# ProPrj_EMU_Multi_LED_Button_PCB_rev1_1.net
KiCad netlist of a schematic drawn in EasyEDA Pro
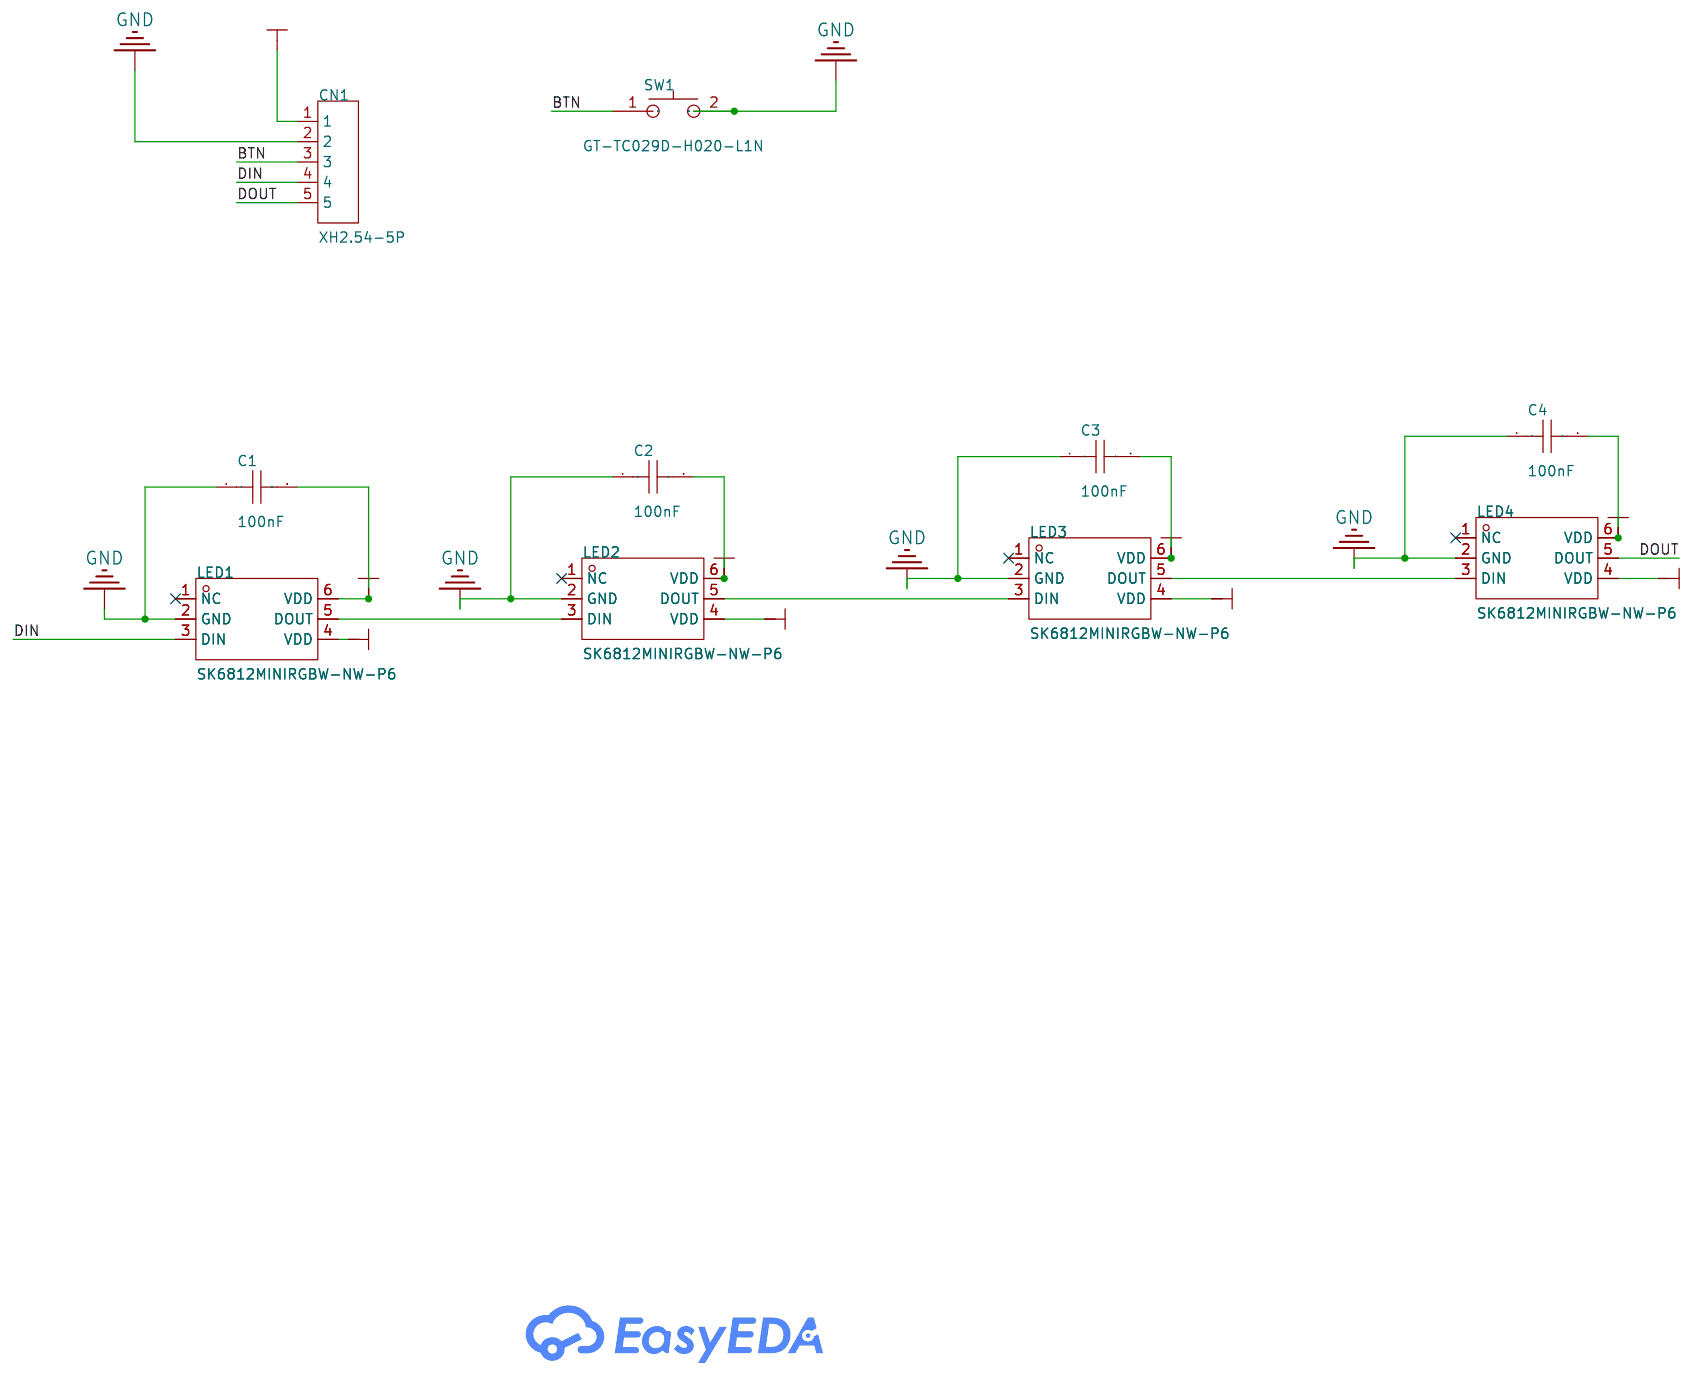
[diagram p0: schematic sheet]

(export (version "E")
  (design (tool "Eeschema 10.0.6"))
  (components
    (comp (ref "C1")
      (value "100nF")
      (footprint "easyedapro:C0603")
      (description "Capacitance:100nF Tolerance:±10% Tolerance:±10% Voltage Rating:50V Temperature Coefficient:X7R")
      (fields
        (field (name "Manufacturer Part") "CC0603KRX7R9BB104")
        (field (name "Manufacturer") "YAGEO(国巨)")
      )
      (libsource (lib "easyedapro") (part "CC0603KRX7R9BB104"))
    )
    (comp (ref "C2")
      (value "100nF")
      (footprint "easyedapro:C0603")
      (description "Capacitance:100nF Tolerance:±10% Tolerance:±10% Voltage Rating:50V Temperature Coefficient:X7R")
      (fields
        (field (name "Manufacturer Part") "CC0603KRX7R9BB104")
        (field (name "Manufacturer") "YAGEO(国巨)")
      )
      (libsource (lib "easyedapro") (part "CC0603KRX7R9BB104"))
    )
    (comp (ref "C3")
      (value "100nF")
      (footprint "easyedapro:C0603")
      (description "Capacitance:100nF Tolerance:±10% Tolerance:±10% Voltage Rating:50V Temperature Coefficient:X7R")
      (fields
        (field (name "Manufacturer Part") "CC0603KRX7R9BB104")
        (field (name "Manufacturer") "YAGEO(国巨)")
      )
      (libsource (lib "easyedapro") (part "CC0603KRX7R9BB104"))
    )
    (comp (ref "C4")
      (value "100nF")
      (footprint "easyedapro:C0603")
      (description "Capacitance:100nF Tolerance:±10% Tolerance:±10% Voltage Rating:50V Temperature Coefficient:X7R")
      (fields
        (field (name "Manufacturer Part") "CC0603KRX7R9BB104")
        (field (name "Manufacturer") "YAGEO(国巨)")
      )
      (libsource (lib "easyedapro") (part "CC0603KRX7R9BB104"))
    )
    (comp (ref "CN1")
      (value "XH2.54-5P")
      (footprint "easyedapro:CONN-TH_5P-P2.54_C9900008095")
      (libsource (lib "easyedapro") (part "XH2.54-5P_C9900017328"))
    )
    (comp (ref "LED1")
      (value "SK6812MINIRGBW-NW-P6")
      (footprint "easyedapro:LED-ARRAY-SMD_6P-L3.7-W3.5-TL-RD-1")
      (fields (field (name "Manufacturer") "欧思科光电"))
      (libsource (lib "easyedapro") (part "SK6812MINIRGBW-NW-P6"))
    )
    (comp (ref "LED2")
      (value "SK6812MINIRGBW-NW-P6")
      (footprint "easyedapro:LED-ARRAY-SMD_6P-L3.7-W3.5-TL-RD-1")
      (fields (field (name "Manufacturer") "欧思科光电"))
      (libsource (lib "easyedapro") (part "SK6812MINIRGBW-NW-P6"))
    )
    (comp (ref "LED3")
      (value "SK6812MINIRGBW-NW-P6")
      (footprint "easyedapro:LED-ARRAY-SMD_6P-L3.7-W3.5-TL-RD-1")
      (fields (field (name "Manufacturer") "欧思科光电"))
      (libsource (lib "easyedapro") (part "SK6812MINIRGBW-NW-P6"))
    )
    (comp (ref "LED4")
      (value "SK6812MINIRGBW-NW-P6")
      (footprint "easyedapro:LED-ARRAY-SMD_6P-L3.7-W3.5-TL-RD-1")
      (fields (field (name "Manufacturer") "欧思科光电"))
      (libsource (lib "easyedapro") (part "SK6812MINIRGBW-NW-P6"))
    )
    (comp (ref "SW1")
      (value "GT-TC029D-H020-L1N")
      (footprint "easyedapro:SW-SMD_L3.9-W2.9-LS4.8")
      (fields (field (name "Manufacturer") "G-Switch(品赞)"))
      (libsource (lib "easyedapro") (part "GT-TC029D-H020-L1"))
    )
  )
  (nets
    (net (code "1") (name "/BTN") (class "Default")
      (node (ref "CN1") (pin "3") (pinfunction "3_3") (pintype "unspecified"))
      (node (ref "SW1") (pin "1") (pinfunction "1_1") (pintype "unspecified"))
    )
    (net (code "2") (name "/DIN") (class "Default")
      (node (ref "CN1") (pin "4") (pinfunction "4_4") (pintype "unspecified"))
      (node (ref "LED1") (pin "3") (pinfunction "DIN_3") (pintype "unspecified"))
    )
    (net (code "3") (name "/DOUT") (class "Default")
      (node (ref "CN1") (pin "5") (pinfunction "5_5") (pintype "unspecified"))
      (node (ref "LED4") (pin "5") (pinfunction "DOUT_5") (pintype "unspecified"))
    )
    (net (code "4") (name "GND") (class "Default")
      (node (ref "C1") (pin "1") (pinfunction "1_1") (pintype "unspecified"))
      (node (ref "C2") (pin "1") (pinfunction "1_1") (pintype "unspecified"))
      (node (ref "C3") (pin "1") (pinfunction "1_1") (pintype "unspecified"))
      (node (ref "C4") (pin "1") (pinfunction "1_1") (pintype "unspecified"))
      (node (ref "CN1") (pin "2") (pinfunction "2_2") (pintype "unspecified"))
      (node (ref "LED1") (pin "2") (pinfunction "GND_2") (pintype "unspecified"))
      (node (ref "LED2") (pin "2") (pinfunction "GND_2") (pintype "unspecified"))
      (node (ref "LED3") (pin "2") (pinfunction "GND_2") (pintype "unspecified"))
      (node (ref "LED4") (pin "2") (pinfunction "GND_2") (pintype "unspecified"))
      (node (ref "SW1") (pin "2") (pinfunction "2_2") (pintype "unspecified"))
    )
    (net (code "5") (name "Net-(LED1-DOUT)") (class "Default")
      (node (ref "LED1") (pin "5") (pinfunction "DOUT_5") (pintype "unspecified"))
      (node (ref "LED2") (pin "3") (pinfunction "DIN_3") (pintype "unspecified"))
    )
    (net (code "6") (name "Net-(LED2-DOUT)") (class "Default")
      (node (ref "LED2") (pin "5") (pinfunction "DOUT_5") (pintype "unspecified"))
      (node (ref "LED3") (pin "3") (pinfunction "DIN_3") (pintype "unspecified"))
    )
    (net (code "7") (name "Net-(LED3-DOUT)") (class "Default")
      (node (ref "LED3") (pin "5") (pinfunction "DOUT_5") (pintype "unspecified"))
      (node (ref "LED4") (pin "3") (pinfunction "DIN_3") (pintype "unspecified"))
    )
    (net (code "8") (name "VCC") (class "Default")
      (node (ref "C1") (pin "2") (pinfunction "2_2") (pintype "unspecified"))
      (node (ref "C2") (pin "2") (pinfunction "2_2") (pintype "unspecified"))
      (node (ref "C3") (pin "2") (pinfunction "2_2") (pintype "unspecified"))
      (node (ref "C4") (pin "2") (pinfunction "2_2") (pintype "unspecified"))
      (node (ref "CN1") (pin "1") (pinfunction "1_1") (pintype "unspecified"))
      (node (ref "LED1") (pin "4") (pinfunction "VDD_4") (pintype "unspecified"))
      (node (ref "LED1") (pin "6") (pinfunction "VDD_6") (pintype "unspecified"))
      (node (ref "LED2") (pin "4") (pinfunction "VDD_4") (pintype "unspecified"))
      (node (ref "LED2") (pin "6") (pinfunction "VDD_6") (pintype "unspecified"))
      (node (ref "LED3") (pin "4") (pinfunction "VDD_4") (pintype "unspecified"))
      (node (ref "LED3") (pin "6") (pinfunction "VDD_6") (pintype "unspecified"))
      (node (ref "LED4") (pin "4") (pinfunction "VDD_4") (pintype "unspecified"))
      (node (ref "LED4") (pin "6") (pinfunction "VDD_6") (pintype "unspecified"))
    )
    (net (code "9") (name "unconnected-(LED1-NC-Pad1)") (class "Default")
      (node (ref "LED1") (pin "1") (pinfunction "NC_1") (pintype "unspecified+no_connect"))
    )
    (net (code "10") (name "unconnected-(LED2-NC-Pad1)") (class "Default")
      (node (ref "LED2") (pin "1") (pinfunction "NC_1") (pintype "unspecified+no_connect"))
    )
    (net (code "11") (name "unconnected-(LED3-NC-Pad1)") (class "Default")
      (node (ref "LED3") (pin "1") (pinfunction "NC_1") (pintype "unspecified+no_connect"))
    )
    (net (code "12") (name "unconnected-(LED4-NC-Pad1)") (class "Default")
      (node (ref "LED4") (pin "1") (pinfunction "NC_1") (pintype "unspecified+no_connect"))
    )
  )
)
